# analog_v2.net
KiCad netlist of a schematic drawn in EAGLE
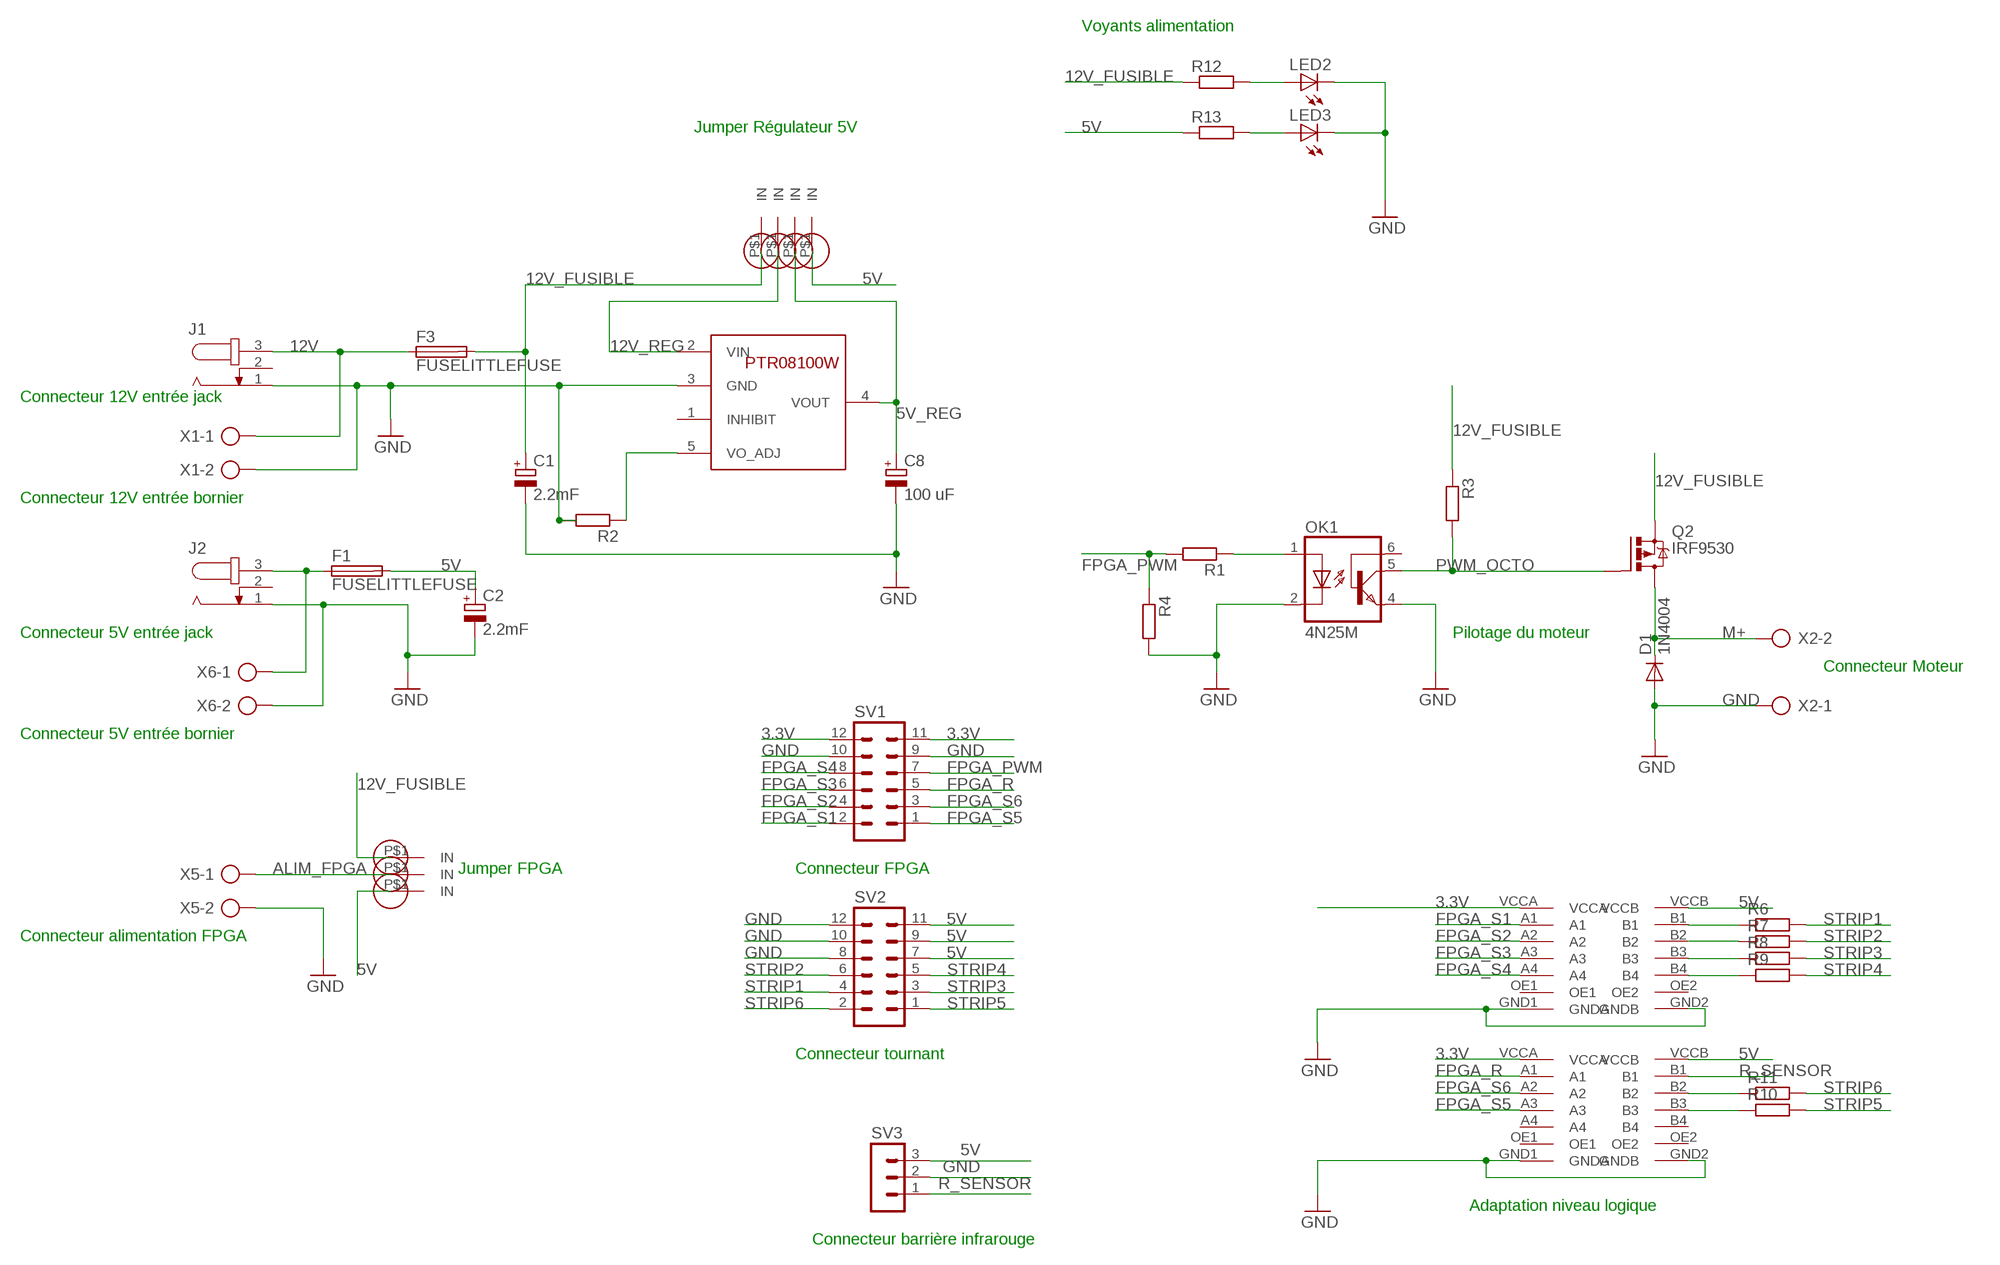
[diagram p0: schematic, sheet 1]

(export (version "E")
  (design (tool "Eeschema 10.0.6"))
  (components
    (comp (ref "C1")
      (value "2.2mF")
      (footprint "eagle-import:E7,5-16")
      (libsource (lib "eagle-import") (part "CPOL-EUE7.5-16"))
    )
    (comp (ref "C2")
      (value "2.2mF")
      (footprint "eagle-import:E7,5-16")
      (libsource (lib "eagle-import") (part "CPOL-EUE7.5-16"))
    )
    (comp (ref "C8")
      (value "100 uF")
      (footprint "eagle-import:E2,5-7")
      (libsource (lib "eagle-import") (part "CPOL-EUE2.5-7"))
    )
    (comp (ref "D1")
      (value "1N4004")
      (footprint "eagle-import:DO41-10")
      (libsource (lib "eagle-import") (part "1N4004"))
    )
    (comp (ref "F1")
      (value "FUSELITTLEFUSE")
      (footprint "eagle-import:LITTLEFUSE")
      (fields (field (name "OC_FARNELL") "unknown") (field (name "OC_NEWARK") "unknown"))
      (libsource (lib "eagle-import") (part "FUSELITTLEFUSE"))
    )
    (comp (ref "F3")
      (value "FUSELITTLEFUSE")
      (footprint "eagle-import:LITTLEFUSE")
      (libsource (lib "eagle-import") (part "FUSELITTLEFUSE"))
    )
    (comp (ref "J1")
      (value "JACK-PLUG1")
      (footprint "eagle-import:SPC4078")
      (libsource (lib "eagle-import") (part "JACK-PLUG1"))
    )
    (comp (ref "J2")
      (value "JACK-PLUG1")
      (footprint "eagle-import:SPC4078")
      (fields (field (name "OC_FARNELL") "unknown") (field (name "OC_NEWARK") "unknown"))
      (libsource (lib "eagle-import") (part "JACK-PLUG1"))
    )
    (comp (ref "LED2")
      (value "LED5MM")
      (footprint "eagle-import:LED5MM")
      (libsource (lib "eagle-import") (part "LED5MM"))
    )
    (comp (ref "LED3")
      (value "LED5MM")
      (footprint "eagle-import:LED5MM")
      (libsource (lib "eagle-import") (part "LED5MM"))
    )
    (comp (ref "OK1")
      (value "4N25M")
      (footprint "eagle-import:DIL06")
      (fields
        (field (name "MPN") "4N25-M")
        (field (name "MPN_1") "4N25-M")
        (field (name "OC_FARNELL") "1021349")
        (field (name "OC_NEWARK") "98K9084")
      )
      (libsource (lib "eagle-import") (part "4N?M25"))
    )
    (comp (ref "Q2")
      (value "IRF9530")
      (footprint "eagle-import:TO220BV")
      (libsource (lib "eagle-import") (part "IRF9530"))
    )
    (comp (ref "R1")
      (value "R-EU_0207/10")
      (footprint "eagle-import:0207_10")
      (libsource (lib "eagle-import") (part "R-EU_0207/10"))
    )
    (comp (ref "R2")
      (value "R-EU_0207/10")
      (footprint "eagle-import:0207_10")
      (libsource (lib "eagle-import") (part "R-EU_0207/10"))
    )
    (comp (ref "R3")
      (value "R-EU_0207/10")
      (footprint "eagle-import:0207_10")
      (libsource (lib "eagle-import") (part "R-EU_0207/10"))
    )
    (comp (ref "R4")
      (value "R-EU_0207/10")
      (footprint "eagle-import:0207_10")
      (libsource (lib "eagle-import") (part "R-EU_0207/10"))
    )
    (comp (ref "R6")
      (value "R-EU_0207/10")
      (footprint "eagle-import:0207_10")
      (libsource (lib "eagle-import") (part "R-EU_0207/10"))
    )
    (comp (ref "R7")
      (value "R-EU_0207/10")
      (footprint "eagle-import:0207_10")
      (libsource (lib "eagle-import") (part "R-EU_0207/10"))
    )
    (comp (ref "R8")
      (value "R-EU_0207/10")
      (footprint "eagle-import:0207_10")
      (libsource (lib "eagle-import") (part "R-EU_0207/10"))
    )
    (comp (ref "R9")
      (value "R-EU_0207/10")
      (footprint "eagle-import:0207_10")
      (libsource (lib "eagle-import") (part "R-EU_0207/10"))
    )
    (comp (ref "R10")
      (value "R-EU_0207/10")
      (footprint "eagle-import:0207_10")
      (libsource (lib "eagle-import") (part "R-EU_0207/10"))
    )
    (comp (ref "R11")
      (value "R-EU_0207/10")
      (footprint "eagle-import:0207_10")
      (libsource (lib "eagle-import") (part "R-EU_0207/10"))
    )
    (comp (ref "R12")
      (value "R-EU_0207/10")
      (footprint "eagle-import:0207_10")
      (libsource (lib "eagle-import") (part "R-EU_0207/10"))
    )
    (comp (ref "R13")
      (value "R-EU_0207/10")
      (footprint "eagle-import:0207_10")
      (libsource (lib "eagle-import") (part "R-EU_0207/10"))
    )
    (comp (ref "SV1")
      (value "MA06-2")
      (footprint "eagle-import:MA06-2")
      (libsource (lib "eagle-import") (part "MA06-2"))
    )
    (comp (ref "SV2")
      (value "MA06-2")
      (footprint "eagle-import:MA06-2")
      (fields (field (name "OC_FARNELL") "unknown") (field (name "OC_NEWARK") "unknown"))
      (libsource (lib "eagle-import") (part "MA06-2"))
    )
    (comp (ref "SV3")
      (value "MA03-1")
      (footprint "eagle-import:MA03-1")
      (libsource (lib "eagle-import") (part "MA03-1"))
    )
    (comp (ref "U$1")
      (value "TXB0104")
      (footprint "eagle-import:TXB0104")
      (libsource (lib "eagle-import") (part "TXB0104"))
    )
    (comp (ref "U$2")
      (value "TXB0104")
      (footprint "eagle-import:TXB0104")
      (libsource (lib "eagle-import") (part "TXB0104"))
    )
    (comp (ref "U$3")
      (value "JUMPER_CONNECTOR")
      (footprint "eagle-import:JUMPER_CONNECTOR")
      (libsource (lib "eagle-import") (part "JUMPER_CONNECTOR"))
    )
    (comp (ref "U$4")
      (value "JUMPER_CONNECTOR")
      (footprint "eagle-import:JUMPER_CONNECTOR")
      (libsource (lib "eagle-import") (part "JUMPER_CONNECTOR"))
    )
    (comp (ref "U$5")
      (value "JUMPER_CONNECTOR")
      (footprint "eagle-import:JUMPER_CONNECTOR")
      (libsource (lib "eagle-import") (part "JUMPER_CONNECTOR"))
    )
    (comp (ref "U$6")
      (value "JUMPER_CONNECTOR")
      (footprint "eagle-import:JUMPER_CONNECTOR")
      (libsource (lib "eagle-import") (part "JUMPER_CONNECTOR"))
    )
    (comp (ref "U$7")
      (value "JUMPER_CONNECTOR")
      (footprint "eagle-import:JUMPER_CONNECTOR")
      (libsource (lib "eagle-import") (part "JUMPER_CONNECTOR"))
    )
    (comp (ref "U$10")
      (value "JUMPER_CONNECTOR")
      (footprint "eagle-import:JUMPER_CONNECTOR")
      (libsource (lib "eagle-import") (part "JUMPER_CONNECTOR"))
    )
    (comp (ref "U$12")
      (value "JUMPER_CONNECTOR")
      (footprint "eagle-import:JUMPER_CONNECTOR")
      (libsource (lib "eagle-import") (part "JUMPER_CONNECTOR"))
    )
    (comp (ref "U2")
      (value "PTR08100W")
      (footprint "eagle-import:PTR08100W")
      (libsource (lib "eagle-import") (part "PTR08100W"))
    )
    (comp (ref "X1")
      (value "AK500/2")
      (footprint "eagle-import:AK500_2")
      (libsource (lib "eagle-import") (part "AK500/2"))
    )
    (comp (ref "X2")
      (value "AK500/2")
      (footprint "eagle-import:AK500_2")
      (libsource (lib "eagle-import") (part "AK500/2"))
    )
    (comp (ref "X5")
      (value "AK500/2")
      (footprint "eagle-import:AK500_2")
      (fields (field (name "OC_FARNELL") "unknown") (field (name "OC_NEWARK") "unknown"))
      (libsource (lib "eagle-import") (part "AK500/2"))
    )
    (comp (ref "X6")
      (value "AK500/2")
      (footprint "eagle-import:AK500_2")
      (fields (field (name "OC_FARNELL") "unknown") (field (name "OC_NEWARK") "unknown"))
      (libsource (lib "eagle-import") (part "AK500/2"))
    )
  )
  (nets
    (net (code "1") (name "/3.3V") (class "Default")
      (node (ref "SV1") (pin "11") (pinfunction "11_11") (pintype "passive"))
      (node (ref "SV1") (pin "12") (pinfunction "12_12") (pintype "passive"))
      (node (ref "U$1") (pin "VCCA") (pinfunction "VCCA_VCCA") (pintype "bidirectional"))
      (node (ref "U$2") (pin "VCCA") (pinfunction "VCCA_VCCA") (pintype "bidirectional"))
    )
    (net (code "2") (name "/5V") (class "Default")
      (node (ref "C2") (pin "+") (pinfunction "+_+") (pintype "passive"))
      (node (ref "F1") (pin "2") (pinfunction "2_2") (pintype "passive"))
      (node (ref "R13") (pin "1") (pinfunction "1_1") (pintype "passive"))
      (node (ref "SV2") (pin "11") (pinfunction "11_11") (pintype "passive"))
      (node (ref "SV2") (pin "7") (pinfunction "7_7") (pintype "passive"))
      (node (ref "SV2") (pin "9") (pinfunction "9_9") (pintype "passive"))
      (node (ref "SV3") (pin "3") (pinfunction "3_3") (pintype "passive"))
      (node (ref "U$1") (pin "VCCB") (pinfunction "VCCB_VCCB") (pintype "bidirectional"))
      (node (ref "U$10") (pin "P$1") (pinfunction "IN_P$1") (pintype "bidirectional"))
      (node (ref "U$2") (pin "VCCB") (pinfunction "VCCB_VCCB") (pintype "bidirectional"))
      (node (ref "U$5") (pin "P$1") (pinfunction "IN_P$1") (pintype "bidirectional"))
    )
    (net (code "3") (name "/5V_REG") (class "Default")
      (node (ref "C8") (pin "+") (pinfunction "+_+") (pintype "passive"))
      (node (ref "U$12") (pin "P$1") (pinfunction "IN_P$1") (pintype "bidirectional"))
      (node (ref "U2") (pin "4") (pinfunction "VOUT_4") (pintype "bidirectional"))
    )
    (net (code "4") (name "/12V") (class "Default")
      (node (ref "F3") (pin "1") (pinfunction "1_1") (pintype "passive"))
      (node (ref "J1") (pin "3") (pinfunction "3_3") (pintype "passive"))
      (node (ref "X1") (pin "1") (pinfunction "KL_1") (pintype "passive"))
    )
    (net (code "5") (name "/12V_FUSIBLE") (class "Default")
      (node (ref "C1") (pin "+") (pinfunction "+_+") (pintype "passive"))
      (node (ref "F3") (pin "2") (pinfunction "2_2") (pintype "passive"))
      (node (ref "Q2") (pin "S") (pinfunction "S_S") (pintype "passive"))
      (node (ref "R12") (pin "1") (pinfunction "1_1") (pintype "passive"))
      (node (ref "R3") (pin "1") (pinfunction "1_1") (pintype "passive"))
      (node (ref "U$3") (pin "P$1") (pinfunction "IN_P$1") (pintype "bidirectional"))
      (node (ref "U$6") (pin "P$1") (pinfunction "IN_P$1") (pintype "bidirectional"))
    )
    (net (code "6") (name "/12V_REG") (class "Default")
      (node (ref "U$7") (pin "P$1") (pinfunction "IN_P$1") (pintype "bidirectional"))
      (node (ref "U2") (pin "2") (pinfunction "VIN_2") (pintype "bidirectional"))
    )
    (net (code "7") (name "/ALIM_FPGA") (class "Default")
      (node (ref "U$4") (pin "P$1") (pinfunction "IN_P$1") (pintype "bidirectional"))
      (node (ref "X5") (pin "1") (pinfunction "KL_1") (pintype "passive"))
    )
    (net (code "8") (name "/FPGA_PWM") (class "Default")
      (node (ref "R1") (pin "2") (pinfunction "2_2") (pintype "passive"))
      (node (ref "R4") (pin "1") (pinfunction "1_1") (pintype "passive"))
      (node (ref "SV1") (pin "7") (pinfunction "7_7") (pintype "passive"))
    )
    (net (code "9") (name "/FPGA_R") (class "Default")
      (node (ref "SV1") (pin "5") (pinfunction "5_5") (pintype "passive"))
      (node (ref "U$2") (pin "A1") (pinfunction "A1_A1") (pintype "bidirectional"))
    )
    (net (code "10") (name "/FPGA_S1") (class "Default")
      (node (ref "SV1") (pin "2") (pinfunction "2_2") (pintype "passive"))
      (node (ref "U$1") (pin "A1") (pinfunction "A1_A1") (pintype "bidirectional"))
    )
    (net (code "11") (name "/FPGA_S2") (class "Default")
      (node (ref "SV1") (pin "4") (pinfunction "4_4") (pintype "passive"))
      (node (ref "U$1") (pin "A2") (pinfunction "A2_A2") (pintype "bidirectional"))
    )
    (net (code "12") (name "/FPGA_S3") (class "Default")
      (node (ref "SV1") (pin "6") (pinfunction "6_6") (pintype "passive"))
      (node (ref "U$1") (pin "A3") (pinfunction "A3_A3") (pintype "bidirectional"))
    )
    (net (code "13") (name "/FPGA_S4") (class "Default")
      (node (ref "SV1") (pin "8") (pinfunction "8_8") (pintype "passive"))
      (node (ref "U$1") (pin "A4") (pinfunction "A4_A4") (pintype "bidirectional"))
    )
    (net (code "14") (name "/FPGA_S5") (class "Default")
      (node (ref "SV1") (pin "1") (pinfunction "1_1") (pintype "passive"))
      (node (ref "U$2") (pin "A3") (pinfunction "A3_A3") (pintype "bidirectional"))
    )
    (net (code "15") (name "/FPGA_S6") (class "Default")
      (node (ref "SV1") (pin "3") (pinfunction "3_3") (pintype "passive"))
      (node (ref "U$2") (pin "A2") (pinfunction "A2_A2") (pintype "bidirectional"))
    )
    (net (code "16") (name "/M+") (class "Default")
      (node (ref "D1") (pin "C") (pinfunction "C_C") (pintype "passive"))
      (node (ref "Q2") (pin "D") (pinfunction "D_D") (pintype "passive"))
      (node (ref "X2") (pin "2") (pinfunction "KL_2") (pintype "passive"))
    )
    (net (code "17") (name "/PWM_OCTO") (class "Default")
      (node (ref "OK1") (pin "5") (pinfunction "COL_5") (pintype "passive"))
      (node (ref "Q2") (pin "G") (pinfunction "G_G") (pintype "passive"))
      (node (ref "R3") (pin "2") (pinfunction "2_2") (pintype "passive"))
    )
    (net (code "18") (name "/R_SENSOR") (class "Default")
      (node (ref "SV3") (pin "1") (pinfunction "1_1") (pintype "passive"))
      (node (ref "U$2") (pin "B1") (pinfunction "B1_B1") (pintype "bidirectional"))
    )
    (net (code "19") (name "/STRIP1") (class "Default")
      (node (ref "R6") (pin "2") (pinfunction "2_2") (pintype "passive"))
      (node (ref "SV2") (pin "4") (pinfunction "4_4") (pintype "passive"))
    )
    (net (code "20") (name "/STRIP2") (class "Default")
      (node (ref "R7") (pin "2") (pinfunction "2_2") (pintype "passive"))
      (node (ref "SV2") (pin "6") (pinfunction "6_6") (pintype "passive"))
    )
    (net (code "21") (name "/STRIP3") (class "Default")
      (node (ref "R8") (pin "2") (pinfunction "2_2") (pintype "passive"))
      (node (ref "SV2") (pin "3") (pinfunction "3_3") (pintype "passive"))
    )
    (net (code "22") (name "/STRIP4") (class "Default")
      (node (ref "R9") (pin "2") (pinfunction "2_2") (pintype "passive"))
      (node (ref "SV2") (pin "5") (pinfunction "5_5") (pintype "passive"))
    )
    (net (code "23") (name "/STRIP5") (class "Default")
      (node (ref "R10") (pin "2") (pinfunction "2_2") (pintype "passive"))
      (node (ref "SV2") (pin "1") (pinfunction "1_1") (pintype "passive"))
    )
    (net (code "24") (name "/STRIP6") (class "Default")
      (node (ref "R11") (pin "2") (pinfunction "2_2") (pintype "passive"))
      (node (ref "SV2") (pin "2") (pinfunction "2_2") (pintype "passive"))
    )
    (net (code "25") (name "GND") (class "Default")
      (node (ref "C1") (pin "-") (pinfunction "-_-") (pintype "passive"))
      (node (ref "C2") (pin "-") (pinfunction "-_-") (pintype "passive"))
      (node (ref "C8") (pin "-") (pinfunction "-_-") (pintype "passive"))
      (node (ref "D1") (pin "A") (pinfunction "A_A") (pintype "passive"))
      (node (ref "J1") (pin "1") (pinfunction "1_1") (pintype "passive"))
      (node (ref "J2") (pin "1") (pinfunction "1_1") (pintype "passive"))
      (node (ref "LED2") (pin "K") (pinfunction "C_K") (pintype "passive"))
      (node (ref "LED3") (pin "K") (pinfunction "C_K") (pintype "passive"))
      (node (ref "OK1") (pin "2") (pinfunction "C_2") (pintype "passive"))
      (node (ref "OK1") (pin "4") (pinfunction "EMI_4") (pintype "passive"))
      (node (ref "R2") (pin "2") (pinfunction "2_2") (pintype "passive"))
      (node (ref "R4") (pin "2") (pinfunction "2_2") (pintype "passive"))
      (node (ref "SV1") (pin "10") (pinfunction "10_10") (pintype "passive"))
      (node (ref "SV1") (pin "9") (pinfunction "9_9") (pintype "passive"))
      (node (ref "SV2") (pin "10") (pinfunction "10_10") (pintype "passive"))
      (node (ref "SV2") (pin "12") (pinfunction "12_12") (pintype "passive"))
      (node (ref "SV2") (pin "8") (pinfunction "8_8") (pintype "passive"))
      (node (ref "SV3") (pin "2") (pinfunction "2_2") (pintype "passive"))
      (node (ref "U$1") (pin "GND1") (pinfunction "GNDA_GND1") (pintype "bidirectional"))
      (node (ref "U$1") (pin "GND2") (pinfunction "GNDB_GND2") (pintype "bidirectional"))
      (node (ref "U$2") (pin "GND1") (pinfunction "GNDA_GND1") (pintype "bidirectional"))
      (node (ref "U$2") (pin "GND2") (pinfunction "GNDB_GND2") (pintype "bidirectional"))
      (node (ref "U2") (pin "3") (pinfunction "GND_3") (pintype "bidirectional"))
      (node (ref "X1") (pin "2") (pinfunction "KL_2") (pintype "passive"))
      (node (ref "X2") (pin "1") (pinfunction "KL_1") (pintype "passive"))
      (node (ref "X5") (pin "2") (pinfunction "KL_2") (pintype "passive"))
      (node (ref "X6") (pin "2") (pinfunction "KL_2") (pintype "passive"))
    )
    (net (code "26") (name "Net-(LED2-PadA)") (class "Default")
      (node (ref "LED2") (pin "A") (pinfunction "A_A") (pintype "passive"))
      (node (ref "R12") (pin "2") (pinfunction "2_2") (pintype "passive"))
    )
    (net (code "27") (name "Net-(LED3-PadA)") (class "Default")
      (node (ref "LED3") (pin "A") (pinfunction "A_A") (pintype "passive"))
      (node (ref "R13") (pin "2") (pinfunction "2_2") (pintype "passive"))
    )
    (net (code "28") (name "Net-(OK1-A)") (class "Default")
      (node (ref "OK1") (pin "1") (pinfunction "A_1") (pintype "passive"))
      (node (ref "R1") (pin "1") (pinfunction "1_1") (pintype "passive"))
    )
    (net (code "29") (name "Net-(R6-Pad1)") (class "Default")
      (node (ref "R6") (pin "1") (pinfunction "1_1") (pintype "passive"))
      (node (ref "U$1") (pin "B1") (pinfunction "B1_B1") (pintype "bidirectional"))
    )
    (net (code "30") (name "Net-(R7-Pad1)") (class "Default")
      (node (ref "R7") (pin "1") (pinfunction "1_1") (pintype "passive"))
      (node (ref "U$1") (pin "B2") (pinfunction "B2_B2") (pintype "bidirectional"))
    )
    (net (code "31") (name "Net-(R8-Pad1)") (class "Default")
      (node (ref "R8") (pin "1") (pinfunction "1_1") (pintype "passive"))
      (node (ref "U$1") (pin "B3") (pinfunction "B3_B3") (pintype "bidirectional"))
    )
    (net (code "32") (name "Net-(R9-Pad1)") (class "Default")
      (node (ref "R9") (pin "1") (pinfunction "1_1") (pintype "passive"))
      (node (ref "U$1") (pin "B4") (pinfunction "B4_B4") (pintype "bidirectional"))
    )
    (net (code "33") (name "Net-(R10-Pad1)") (class "Default")
      (node (ref "R10") (pin "1") (pinfunction "1_1") (pintype "passive"))
      (node (ref "U$2") (pin "B3") (pinfunction "B3_B3") (pintype "bidirectional"))
    )
    (net (code "34") (name "Net-(R11-Pad1)") (class "Default")
      (node (ref "R11") (pin "1") (pinfunction "1_1") (pintype "passive"))
      (node (ref "U$2") (pin "B2") (pinfunction "B2_B2") (pintype "bidirectional"))
    )
    (net (code "35") (name "Net-(U2-VO_ADJ)") (class "Default")
      (node (ref "R2") (pin "1") (pinfunction "1_1") (pintype "passive"))
      (node (ref "U2") (pin "5") (pinfunction "VO_ADJ_5") (pintype "bidirectional"))
    )
    (net (code "36") (name "Net-(X6A-KL)") (class "Default")
      (node (ref "F1") (pin "1") (pinfunction "1_1") (pintype "passive"))
      (node (ref "J2") (pin "3") (pinfunction "3_3") (pintype "passive"))
      (node (ref "X6") (pin "1") (pinfunction "KL_1") (pintype "passive"))
    )
    (net (code "37") (name "unconnected-(J1-Pad2)") (class "Default")
      (node (ref "J1") (pin "2") (pinfunction "2_2") (pintype "passive"))
    )
    (net (code "38") (name "unconnected-(J2-Pad2)") (class "Default")
      (node (ref "J2") (pin "2") (pinfunction "2_2") (pintype "passive"))
    )
    (net (code "39") (name "unconnected-(OK1-BAS-Pad6)") (class "Default")
      (node (ref "OK1") (pin "6") (pinfunction "BAS_6") (pintype "passive"))
    )
    (net (code "40") (name "unconnected-(U$1-PadOE1)") (class "Default")
      (node (ref "U$1") (pin "OE1") (pinfunction "OE1_OE1") (pintype "bidirectional"))
    )
    (net (code "41") (name "unconnected-(U$1-PadOE2)") (class "Default")
      (node (ref "U$1") (pin "OE2") (pinfunction "OE2_OE2") (pintype "bidirectional"))
    )
    (net (code "42") (name "unconnected-(U$2-PadA4)") (class "Default")
      (node (ref "U$2") (pin "A4") (pinfunction "A4_A4") (pintype "bidirectional"))
    )
    (net (code "43") (name "unconnected-(U$2-PadB4)") (class "Default")
      (node (ref "U$2") (pin "B4") (pinfunction "B4_B4") (pintype "bidirectional"))
    )
    (net (code "44") (name "unconnected-(U$2-PadOE1)") (class "Default")
      (node (ref "U$2") (pin "OE1") (pinfunction "OE1_OE1") (pintype "bidirectional"))
    )
    (net (code "45") (name "unconnected-(U$2-PadOE2)") (class "Default")
      (node (ref "U$2") (pin "OE2") (pinfunction "OE2_OE2") (pintype "bidirectional"))
    )
    (net (code "46") (name "unconnected-(U2-INHIBIT-Pad1)") (class "Default")
      (node (ref "U2") (pin "1") (pinfunction "INHIBIT_1") (pintype "bidirectional"))
    )
  )
)
